# ADCMP.net
KiCad netlist of a schematic drawn in Altium Designer
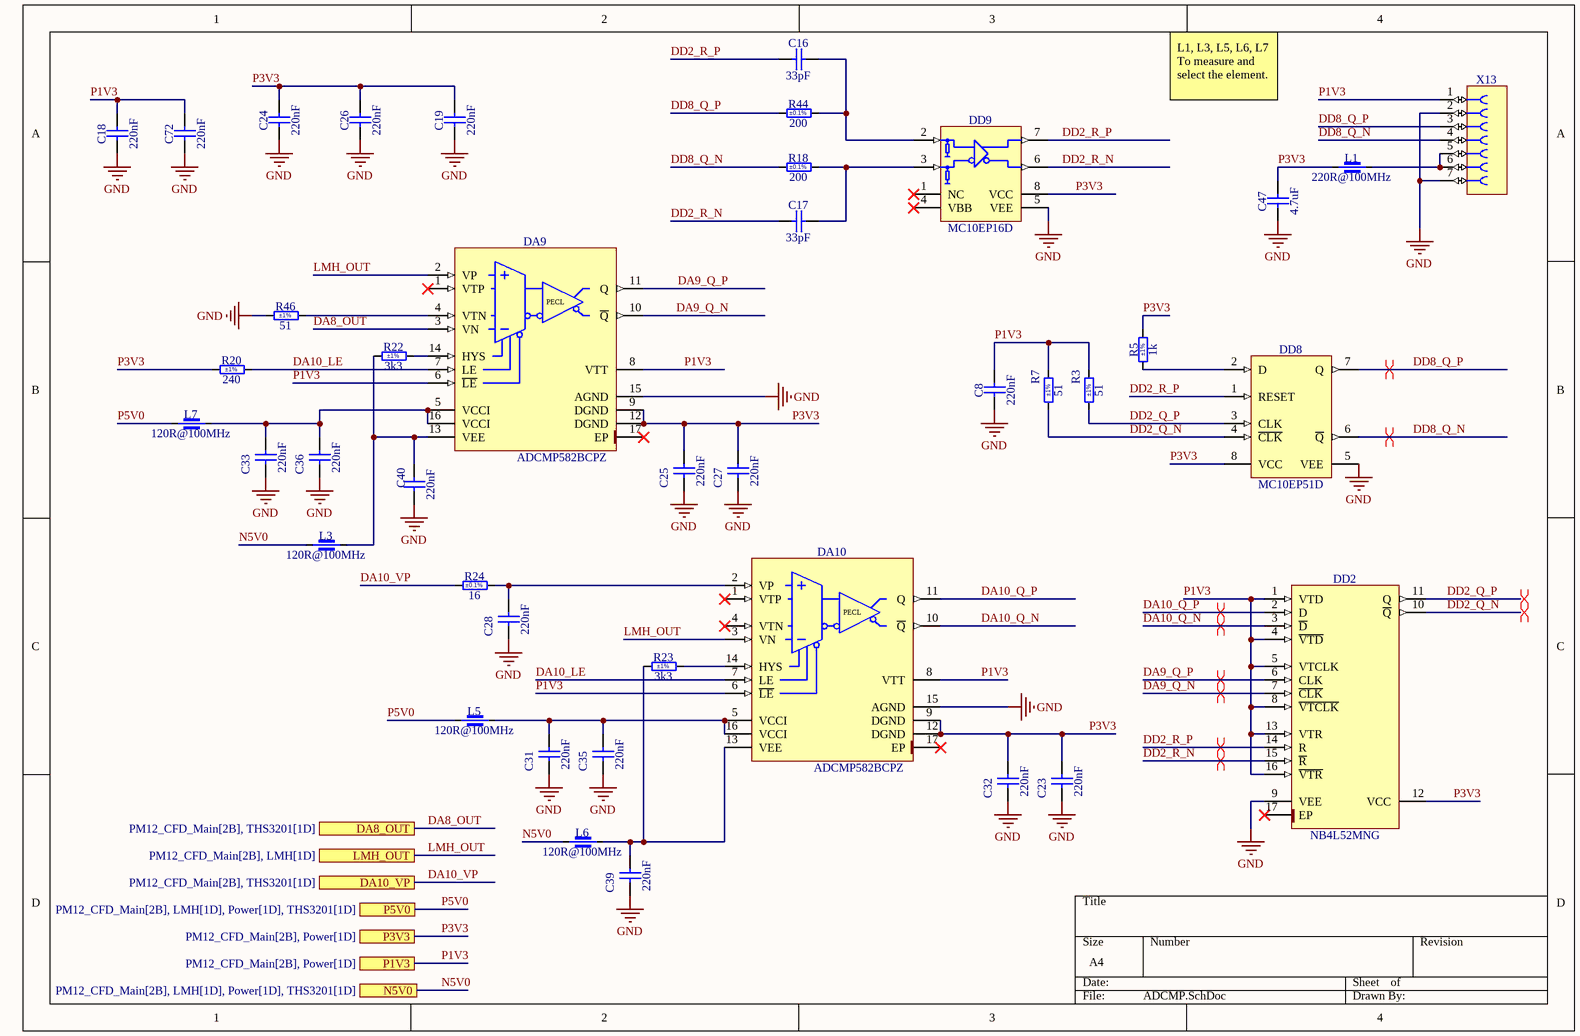
[diagram p0: ADCMP.SchDoc]

(export (version "E")
  (design (tool "Eeschema 10.0.6"))
  (components
    (comp (ref "C8")
      (value "220nF")
      (footprint "CAPC2012X135N")
      (description "Non-polarised capacitor")
      (fields
        (field (name "PART NUMBER") "CC0805_220NF_50V_10%_X7R")
        (field (name "VOLTAGE") "50V")
        (field (name "AUTHOR") "CERN DEM JLC")
      )
      (libsource (lib "Capacitors") (part "Capacitor - non polarized"))
    )
    (comp (ref "C16")
      (value "33pF")
      (footprint "CAPC2012X135N")
      (description "Non-polarised capacitor")
      (fields
        (field (name "PART NUMBER") "CC0805_33PF_50V_5%_NP0")
        (field (name "VOLTAGE") "50V")
        (field (name "AUTHOR") "CERN DEM JLC")
      )
      (libsource (lib "Capacitors") (part "Capacitor - non polarized"))
    )
    (comp (ref "C17")
      (value "33pF")
      (footprint "CAPC2012X135N")
      (description "Non-polarised capacitor")
      (fields
        (field (name "PART NUMBER") "CC0805_33PF_50V_5%_NP0")
        (field (name "VOLTAGE") "50V")
        (field (name "AUTHOR") "CERN DEM JLC")
      )
      (libsource (lib "Capacitors") (part "Capacitor - non polarized"))
    )
    (comp (ref "C18")
      (value "220nF")
      (footprint "CAPC1608X87N")
      (description "Non-polarised capacitor")
      (fields
        (field (name "PART NUMBER") "CC0603_220NF_25V_10%_X7R")
        (field (name "VOLTAGE") "25V")
        (field (name "AUTHOR") "CERN DEM JLC")
      )
      (libsource (lib "Capacitors") (part "Capacitor - non polarized"))
    )
    (comp (ref "C19")
      (value "220nF")
      (footprint "CAPC2012X135N")
      (description "Non-polarised capacitor")
      (fields
        (field (name "PART NUMBER") "CC0805_220NF_50V_10%_X7R")
        (field (name "VOLTAGE") "50V")
        (field (name "AUTHOR") "CERN DEM JLC")
      )
      (libsource (lib "Capacitors") (part "Capacitor - non polarized"))
    )
    (comp (ref "C23")
      (value "220nF")
      (footprint "CAPC1608X87N")
      (description "Non-polarised capacitor")
      (fields
        (field (name "PART NUMBER") "CC0603_220NF_25V_10%_X7R")
        (field (name "VOLTAGE") "25V")
        (field (name "AUTHOR") "CERN DEM JLC")
      )
      (libsource (lib "Capacitors") (part "Capacitor - non polarized"))
    )
    (comp (ref "C24")
      (value "220nF")
      (footprint "CAPC2012X135N")
      (description "Non-polarised capacitor")
      (fields
        (field (name "PART NUMBER") "CC0805_220NF_50V_10%_X7R")
        (field (name "VOLTAGE") "50V")
        (field (name "AUTHOR") "CERN DEM JLC")
      )
      (libsource (lib "Capacitors") (part "Capacitor - non polarized"))
    )
    (comp (ref "C25")
      (value "220nF")
      (footprint "CAPC1608X87N")
      (description "Non-polarised capacitor")
      (fields
        (field (name "PART NUMBER") "CC0603_220NF_25V_10%_X7R")
        (field (name "VOLTAGE") "25V")
        (field (name "AUTHOR") "CERN DEM JLC")
      )
      (libsource (lib "Capacitors") (part "Capacitor - non polarized"))
    )
    (comp (ref "C26")
      (value "220nF")
      (footprint "CAPC2012X135N")
      (description "Non-polarised capacitor")
      (fields
        (field (name "PART NUMBER") "CC0805_220NF_50V_10%_X7R")
        (field (name "VOLTAGE") "50V")
        (field (name "AUTHOR") "CERN DEM JLC")
      )
      (libsource (lib "Capacitors") (part "Capacitor - non polarized"))
    )
    (comp (ref "C27")
      (value "220nF")
      (footprint "CAPC1608X87N")
      (description "Non-polarised capacitor")
      (fields
        (field (name "PART NUMBER") "CC0603_220NF_25V_10%_X7R")
        (field (name "VOLTAGE") "25V")
        (field (name "AUTHOR") "CERN DEM JLC")
      )
      (libsource (lib "Capacitors") (part "Capacitor - non polarized"))
    )
    (comp (ref "C28")
      (value "220nF")
      (footprint "CAPC1608X87N")
      (description "Non-polarised capacitor")
      (fields
        (field (name "PART NUMBER") "CC0603_220NF_25V_10%_X7R")
        (field (name "VOLTAGE") "25V")
        (field (name "AUTHOR") "CERN DEM JLC")
      )
      (libsource (lib "Capacitors") (part "Capacitor - non polarized"))
    )
    (comp (ref "C31")
      (value "220nF")
      (footprint "CAPC1608X87N")
      (description "Non-polarised capacitor")
      (fields
        (field (name "PART NUMBER") "CC0603_220NF_25V_10%_X7R")
        (field (name "VOLTAGE") "25V")
        (field (name "AUTHOR") "CERN DEM JLC")
      )
      (libsource (lib "Capacitors") (part "Capacitor - non polarized"))
    )
    (comp (ref "C32")
      (value "220nF")
      (footprint "CAPC1608X87N")
      (description "Non-polarised capacitor")
      (fields
        (field (name "PART NUMBER") "CC0603_220NF_25V_10%_X7R")
        (field (name "VOLTAGE") "25V")
        (field (name "AUTHOR") "CERN DEM JLC")
      )
      (libsource (lib "Capacitors") (part "Capacitor - non polarized"))
    )
    (comp (ref "C33")
      (value "220nF")
      (footprint "CAPC1608X87N")
      (description "Non-polarised capacitor")
      (fields
        (field (name "PART NUMBER") "CC0603_220NF_25V_10%_X7R")
        (field (name "VOLTAGE") "25V")
        (field (name "AUTHOR") "CERN DEM JLC")
      )
      (libsource (lib "Capacitors") (part "Capacitor - non polarized"))
    )
    (comp (ref "C35")
      (value "220nF")
      (footprint "CAPC1608X87N")
      (description "Non-polarised capacitor")
      (fields
        (field (name "PART NUMBER") "CC0603_220NF_25V_10%_X7R")
        (field (name "VOLTAGE") "25V")
        (field (name "AUTHOR") "CERN DEM JLC")
      )
      (libsource (lib "Capacitors") (part "Capacitor - non polarized"))
    )
    (comp (ref "C36")
      (value "220nF")
      (footprint "CAPC1608X87N")
      (description "Non-polarised capacitor")
      (fields
        (field (name "PART NUMBER") "CC0603_220NF_25V_10%_X7R")
        (field (name "VOLTAGE") "25V")
        (field (name "AUTHOR") "CERN DEM JLC")
      )
      (libsource (lib "Capacitors") (part "Capacitor - non polarized"))
    )
    (comp (ref "C39")
      (value "220nF")
      (footprint "CAPC1608X87N")
      (description "Non-polarised capacitor")
      (fields
        (field (name "PART NUMBER") "CC0603_220NF_25V_10%_X7R")
        (field (name "VOLTAGE") "25V")
        (field (name "AUTHOR") "CERN DEM JLC")
      )
      (libsource (lib "Capacitors") (part "Capacitor - non polarized"))
    )
    (comp (ref "C40")
      (value "220nF")
      (footprint "CAPC1608X87N")
      (description "Non-polarised capacitor")
      (fields
        (field (name "PART NUMBER") "CC0603_220NF_25V_10%_X7R")
        (field (name "VOLTAGE") "25V")
        (field (name "AUTHOR") "CERN DEM JLC")
      )
      (libsource (lib "Capacitors") (part "Capacitor - non polarized"))
    )
    (comp (ref "C47")
      (value "4.7uF")
      (footprint "CAPC3216X180N")
      (description "Non-polarised capacitor")
      (fields
        (field (name "PART NUMBER") "CC1206_4.7UF_25V_10%_X7R")
        (field (name "VOLTAGE") "25V")
        (field (name "AUTHOR") "CERN DEM WB")
      )
      (libsource (lib "Capacitors") (part "Capacitor - non polarized"))
    )
    (comp (ref "C72")
      (value "220nF")
      (footprint "CAPC2012X135N")
      (description "Non-polarised capacitor")
      (fields
        (field (name "PART NUMBER") "CC0805_220NF_50V_10%_X7R")
        (field (name "VOLTAGE") "50V")
        (field (name "AUTHOR") "CERN DEM JLC")
      )
      (libsource (lib "Capacitors") (part "Capacitor - non polarized"))
    )
    (comp (ref "DA9")
      (value "ADCMP582BCPZ")
      (footprint "QFN50P300X300X80-17N-S145")
      (description "Ultrafast SiGe Voltage Comparator")
      (fields
        (field (name "MANUFACTURER") "ANALOG DEVICES")
        (field (name "MANUFACTURER PART NUMBER") "ADCMP582BCP")
        (field (name "AUTHOR") "CERN DEM MR")
      )
      (libsource (lib "ICs And Semiconductors") (part "ADCMP582BCPZ"))
    )
    (comp (ref "DA10")
      (value "ADCMP582BCPZ")
      (footprint "QFN50P300X300X80-17N-S145")
      (description "Ultrafast SiGe Voltage Comparator")
      (fields
        (field (name "MANUFACTURER") "ANALOG DEVICES")
        (field (name "MANUFACTURER PART NUMBER") "ADCMP582BCP")
        (field (name "AUTHOR") "CERN DEM MR")
      )
      (libsource (lib "ICs And Semiconductors") (part "ADCMP582BCPZ"))
    )
    (comp (ref "DD2")
      (value "NB4L52MNG")
      (footprint "QFN50P300X300X100-17N-S185")
      (description "2.5 V/3.3 V/5.0 V Differential Data/Clock D Flip-Flop with Reset")
      (fields
        (field (name "MANUFACTURER") "ON SEMICONDUCTOR")
        (field (name "MANUFACTURER PART NUMBER") "NB4L52MN")
        (field (name "AUTHOR") "CERN DEM MR")
      )
      (libsource (lib "ICs And Semiconductors") (part "NB4L52MN"))
    )
    (comp (ref "DD8")
      (value "MC10EP51D")
      (footprint "SOIC127P600X175-8N")
      (description "3.3V/5V ECL D Flip-Flop with Reset and Differential Clock")
      (fields (field (name "MANUFACTURER") "ON SEMICONDUCTOR") (field (name "AUTHOR") "CERN DEM HF"))
      (libsource (lib "ICs And Semiconductors") (part "10EP51"))
    )
    (comp (ref "DD9")
      (value "MC10EP16D")
      (footprint "SOIC127P600X175-8N")
      (description "3.3V / 5V ECL Differential Receiver/Driver")
      (fields (field (name "MANUFACTURER") "ON SEMICONDUCTOR") (field (name "AUTHOR") "CERN DEM HF"))
      (libsource (lib "ICs And Semiconductors") (part "10EP16"))
    )
    (comp (ref "L1")
      (value "220R@100MHz")
      (footprint "INDC2012X105N")
      (fields
        (field (name "PART NUMBER") "IND0805_TDK_MPZ2012S221A")
        (field (name "POWER") "3A")
        (field (name "TOLERANCE") "±25%")
        (field (name "AUTHOR") "CERN DEM HF")
      )
      (libsource (lib "Inductors & Transformers") (part "Ferrite Bead"))
    )
    (comp (ref "L3")
      (value "120R@100MHz")
      (footprint "INDC1608X95N")
      (fields
        (field (name "PART NUMBER") "IND0603_MURATA_BLM18PG121SN1D")
        (field (name "POWER") "2A")
        (field (name "MANUFACTURER") "MURATA")
        (field (name "AUTHOR") "CERN DEM BC")
      )
      (libsource (lib "Inductors & Transformers") (part "Ferrite Bead"))
    )
    (comp (ref "L5")
      (value "120R@100MHz")
      (footprint "INDC1608X95N")
      (fields
        (field (name "PART NUMBER") "IND0603_MURATA_BLM18PG121SN1D")
        (field (name "POWER") "2A")
        (field (name "MANUFACTURER") "MURATA")
        (field (name "AUTHOR") "CERN DEM BC")
      )
      (libsource (lib "Inductors & Transformers") (part "Ferrite Bead"))
    )
    (comp (ref "L6")
      (value "120R@100MHz")
      (footprint "INDC1608X95N")
      (fields
        (field (name "PART NUMBER") "IND0603_MURATA_BLM18PG121SN1D")
        (field (name "POWER") "2A")
        (field (name "MANUFACTURER") "MURATA")
        (field (name "AUTHOR") "CERN DEM BC")
      )
      (libsource (lib "Inductors & Transformers") (part "Ferrite Bead"))
    )
    (comp (ref "L7")
      (value "120R@100MHz")
      (footprint "INDC1608X95N")
      (fields
        (field (name "PART NUMBER") "IND0603_MURATA_BLM18PG121SN1D")
        (field (name "POWER") "2A")
        (field (name "MANUFACTURER") "MURATA")
        (field (name "AUTHOR") "CERN DEM BC")
      )
      (libsource (lib "Inductors & Transformers") (part "Ferrite Bead"))
    )
    (comp (ref "R3")
      (value "51")
      (footprint "RESC2012X60N")
      (description "Resistor - 1%")
      (fields
        (field (name "TOLERANCE") "±1%")
        (field (name "PART NUMBER") "R0805_51R_1%_0.125W_100PPM")
        (field (name "POWER") "0.125W")
        (field (name "AUTHOR") "CERN DEM JLC")
      )
      (libsource (lib "Resistors") (part "Resistor - 1%"))
    )
    (comp (ref "R5")
      (value "1k")
      (footprint "RESC2012X60N")
      (description "Resistor - 1%")
      (fields
        (field (name "TOLERANCE") "±1%")
        (field (name "PART NUMBER") "R0805_1K_1%_0.125W_100PPM")
        (field (name "POWER") "0.125W")
        (field (name "AUTHOR") "CERN DEM JLC")
      )
      (libsource (lib "Resistors") (part "Resistor - 1%"))
    )
    (comp (ref "R7")
      (value "51")
      (footprint "RESC2012X60N")
      (description "Resistor - 1%")
      (fields
        (field (name "TOLERANCE") "±1%")
        (field (name "PART NUMBER") "R0805_51R_1%_0.125W_100PPM")
        (field (name "POWER") "0.125W")
        (field (name "AUTHOR") "CERN DEM JLC")
      )
      (libsource (lib "Resistors") (part "Resistor - 1%"))
    )
    (comp (ref "R18")
      (value "200")
      (footprint "RESC2012X60N")
      (description "Resistor - 0.1%")
      (fields
        (field (name "TOLERANCE") "±0.1%")
        (field (name "PART NUMBER") "R0805_200R_0.1%_0.1W_10PPM")
        (field (name "POWER") "0.1W")
        (field (name "AUTHOR") "CERN DEM JLC")
      )
      (libsource (lib "Resistors") (part "Resistor - 0.1%"))
    )
    (comp (ref "R20")
      (value "240")
      (footprint "RESC1608X55N")
      (description "Resistor - 1%")
      (fields
        (field (name "TOLERANCE") "±1%")
        (field (name "PART NUMBER") "R0603_240R_1%_0.1W_100PPM")
        (field (name "POWER") "0.1W")
        (field (name "AUTHOR") "CERN DEM JLC")
      )
      (libsource (lib "Resistors") (part "Resistor - 1%"))
    )
    (comp (ref "R22")
      (value "3k3")
      (footprint "RESC1608X55N")
      (description "Resistor - 1%")
      (fields
        (field (name "TOLERANCE") "±1%")
        (field (name "PART NUMBER") "R0603_3K3_1%_0.1W_100PPM")
        (field (name "POWER") "0.1W")
        (field (name "AUTHOR") "CERN DEM JLC")
      )
      (libsource (lib "Resistors") (part "Resistor - 1%"))
    )
    (comp (ref "R23")
      (value "3k3")
      (footprint "RESC1608X55N")
      (description "Resistor - 1%")
      (fields
        (field (name "TOLERANCE") "±1%")
        (field (name "PART NUMBER") "R0603_3K3_1%_0.1W_100PPM")
        (field (name "POWER") "0.1W")
        (field (name "AUTHOR") "CERN DEM JLC")
      )
      (libsource (lib "Resistors") (part "Resistor - 1%"))
    )
    (comp (ref "R24")
      (value "16")
      (footprint "RESC1608X64N")
      (description "Resistor - 0.1%")
      (fields
        (field (name "TOLERANCE") "±0.1%")
        (field (name "PART NUMBER") "R0603_16R_0.1%_0.1W_10PPM")
        (field (name "POWER") "0.1W")
        (field (name "AUTHOR") "CERN DEM HF")
      )
      (libsource (lib "Resistors") (part "Resistor - 0.1%"))
    )
    (comp (ref "R44")
      (value "200")
      (footprint "RESC2012X60N")
      (description "Resistor - 0.1%")
      (fields
        (field (name "TOLERANCE") "±0.1%")
        (field (name "PART NUMBER") "R0805_200R_0.1%_0.1W_10PPM")
        (field (name "POWER") "0.1W")
        (field (name "AUTHOR") "CERN DEM JLC")
      )
      (libsource (lib "Resistors") (part "Resistor - 0.1%"))
    )
    (comp (ref "R46")
      (value "51")
      (footprint "RESC1608X55N")
      (description "Resistor - 1%")
      (fields
        (field (name "TOLERANCE") "±1%")
        (field (name "PART NUMBER") "R0603_51R_1%_0.1W_100PPM")
        (field (name "POWER") "0.1W")
        (field (name "AUTHOR") "CERN DEM JLC")
      )
      (libsource (lib "Resistors") (part "Resistor - 1%"))
    )
    (comp (ref "X13")
      (value "Socket 7")
      (footprint "SAMTEC_CES-107-01-T-S")
      (description "Connector 7 Female")
      (fields
        (field (name "PART NUMBER") "SAMTEC_CES-107-01-L-S")
        (field (name "MANUFACTURER") "SAMTEC")
        (field (name "AUTHOR") "CERN DEM HF")
      )
      (libsource (lib "Connectors") (part "Connector 7 Female"))
    )
  )
  (nets
    (net (code "1") (name "/DA8_OUT") (class "Default")
      (node (ref "DA9") (pin "3") (pinfunction "VN_3") (pintype "input"))
    )
    (net (code "2") (name "/DA9_Q_N") (class "Default")
      (node (ref "DA9") (pin "10") (pinfunction "~{Q}_10") (pintype "output"))
      (node (ref "DD2") (pin "7") (pinfunction "~{CLK}_7") (pintype "input"))
    )
    (net (code "3") (name "/DA9_Q_P") (class "Default")
      (node (ref "DA9") (pin "11") (pinfunction "Q_11") (pintype "output"))
      (node (ref "DD2") (pin "6") (pinfunction "CLK_6") (pintype "input"))
    )
    (net (code "4") (name "/DA10_LE") (class "Default")
      (node (ref "DA10") (pin "7") (pinfunction "LE_7") (pintype "input"))
      (node (ref "DA9") (pin "7") (pinfunction "LE_7") (pintype "input"))
      (node (ref "R20") (pin "2") (pinfunction "2_2") (pintype "passive"))
    )
    (net (code "5") (name "/DA10_Q_N") (class "Default")
      (node (ref "DA10") (pin "10") (pinfunction "~{Q}_10") (pintype "output"))
      (node (ref "DD2") (pin "3") (pinfunction "~{D}_3") (pintype "input"))
    )
    (net (code "6") (name "/DA10_Q_P") (class "Default")
      (node (ref "DA10") (pin "11") (pinfunction "Q_11") (pintype "output"))
      (node (ref "DD2") (pin "2") (pinfunction "D_2") (pintype "input"))
    )
    (net (code "7") (name "/DA10_VP") (class "Default")
      (node (ref "R24") (pin "1") (pinfunction "1_1") (pintype "passive"))
    )
    (net (code "8") (name "/DD2_Q_N") (class "Default")
      (node (ref "DD2") (pin "10") (pinfunction "~{Q}_10") (pintype "output"))
      (node (ref "DD8") (pin "4") (pinfunction "~{CLK}_4") (pintype "input"))
      (node (ref "R7") (pin "1") (pinfunction "1_1") (pintype "passive"))
    )
    (net (code "9") (name "/DD2_Q_P") (class "Default")
      (node (ref "DD2") (pin "11") (pinfunction "Q_11") (pintype "output"))
      (node (ref "DD8") (pin "3") (pinfunction "CLK_3") (pintype "input"))
      (node (ref "R3") (pin "1") (pinfunction "1_1") (pintype "passive"))
    )
    (net (code "10") (name "/DD2_R_N") (class "Default")
      (node (ref "C17") (pin "1") (pinfunction "1_1") (pintype "passive"))
      (node (ref "DD2") (pin "15") (pinfunction "~{R}_15") (pintype "input"))
      (node (ref "DD9") (pin "6") (pinfunction "~{Q}_6") (pintype "output"))
    )
    (net (code "11") (name "/DD2_R_P") (class "Default")
      (node (ref "C16") (pin "1") (pinfunction "1_1") (pintype "passive"))
      (node (ref "DD2") (pin "14") (pinfunction "R_14") (pintype "input"))
      (node (ref "DD8") (pin "1") (pinfunction "RESET_1") (pintype "input"))
      (node (ref "DD9") (pin "7") (pinfunction "Q_7") (pintype "output"))
    )
    (net (code "12") (name "/DD8_Q_N") (class "Default")
      (node (ref "DD8") (pin "6") (pinfunction "~{Q}_6") (pintype "output"))
      (node (ref "R18") (pin "1") (pinfunction "1_1") (pintype "passive"))
      (node (ref "X13") (pin "4") (pinfunction "4_4") (pintype "bidirectional"))
    )
    (net (code "13") (name "/DD8_Q_P") (class "Default")
      (node (ref "DD8") (pin "7") (pinfunction "Q_7") (pintype "output"))
      (node (ref "R44") (pin "1") (pinfunction "1_1") (pintype "passive"))
      (node (ref "X13") (pin "3") (pinfunction "3_3") (pintype "bidirectional"))
    )
    (net (code "14") (name "/LMH_OUT") (class "Default")
      (node (ref "DA10") (pin "3") (pinfunction "VN_3") (pintype "input"))
      (node (ref "DA9") (pin "2") (pinfunction "VP_2") (pintype "input"))
    )
    (net (code "15") (name "/N5V0") (class "Default")
      (node (ref "L3") (pin "1") (pinfunction "1_1") (pintype "passive"))
      (node (ref "L6") (pin "1") (pinfunction "1_1") (pintype "passive"))
    )
    (net (code "16") (name "/P1V3") (class "Default")
      (node (ref "C18") (pin "2") (pinfunction "2_2") (pintype "passive"))
      (node (ref "C72") (pin "2") (pinfunction "2_2") (pintype "passive"))
      (node (ref "C8") (pin "2") (pinfunction "2_2") (pintype "passive"))
      (node (ref "DA10") (pin "6") (pinfunction "~{LE}_6") (pintype "input"))
      (node (ref "DA10") (pin "8") (pinfunction "VTT_8") (pintype "power_in"))
      (node (ref "DA9") (pin "6") (pinfunction "~{LE}_6") (pintype "input"))
      (node (ref "DA9") (pin "8") (pinfunction "VTT_8") (pintype "power_in"))
      (node (ref "DD2") (pin "1") (pinfunction "VTD_1") (pintype "input"))
      (node (ref "DD2") (pin "13") (pinfunction "VTR_13") (pintype "input"))
      (node (ref "DD2") (pin "16") (pinfunction "~{VTR}_16") (pintype "input"))
      (node (ref "DD2") (pin "4") (pinfunction "~{VTD}_4") (pintype "input"))
      (node (ref "DD2") (pin "5") (pinfunction "VTCLK_5") (pintype "input"))
      (node (ref "DD2") (pin "8") (pinfunction "~{VTCLK}_8") (pintype "input"))
      (node (ref "R3") (pin "2") (pinfunction "2_2") (pintype "passive"))
      (node (ref "R7") (pin "2") (pinfunction "2_2") (pintype "passive"))
      (node (ref "X13") (pin "1") (pinfunction "1_1") (pintype "bidirectional"))
    )
    (net (code "17") (name "/P3V3") (class "Default")
      (node (ref "C19") (pin "2") (pinfunction "2_2") (pintype "passive"))
      (node (ref "C23") (pin "2") (pinfunction "2_2") (pintype "passive"))
      (node (ref "C24") (pin "2") (pinfunction "2_2") (pintype "passive"))
      (node (ref "C25") (pin "2") (pinfunction "2_2") (pintype "passive"))
      (node (ref "C26") (pin "2") (pinfunction "2_2") (pintype "passive"))
      (node (ref "C27") (pin "2") (pinfunction "2_2") (pintype "passive"))
      (node (ref "C32") (pin "2") (pinfunction "2_2") (pintype "passive"))
      (node (ref "C47") (pin "2") (pinfunction "2_2") (pintype "passive"))
      (node (ref "DA10") (pin "12") (pinfunction "DGND_12") (pintype "power_in"))
      (node (ref "DA10") (pin "9") (pinfunction "DGND_9") (pintype "power_in"))
      (node (ref "DA9") (pin "12") (pinfunction "DGND_12") (pintype "power_in"))
      (node (ref "DA9") (pin "9") (pinfunction "DGND_9") (pintype "power_in"))
      (node (ref "DD2") (pin "12") (pinfunction "VCC_12") (pintype "power_in"))
      (node (ref "DD8") (pin "8") (pinfunction "VCC_8") (pintype "power_in"))
      (node (ref "DD9") (pin "8") (pinfunction "VCC_8") (pintype "power_in"))
      (node (ref "L1") (pin "1") (pinfunction "1_1") (pintype "passive"))
      (node (ref "R20") (pin "1") (pinfunction "1_1") (pintype "passive"))
      (node (ref "R5") (pin "2") (pinfunction "2_2") (pintype "passive"))
    )
    (net (code "18") (name "/P5V0") (class "Default")
      (node (ref "L5") (pin "1") (pinfunction "1_1") (pintype "passive"))
      (node (ref "L7") (pin "1") (pinfunction "1_1") (pintype "passive"))
    )
    (net (code "19") (name "GND") (class "Default")
      (node (ref "C18") (pin "1") (pinfunction "1_1") (pintype "passive"))
      (node (ref "C19") (pin "1") (pinfunction "1_1") (pintype "passive"))
      (node (ref "C23") (pin "1") (pinfunction "1_1") (pintype "passive"))
      (node (ref "C24") (pin "1") (pinfunction "1_1") (pintype "passive"))
      (node (ref "C25") (pin "1") (pinfunction "1_1") (pintype "passive"))
      (node (ref "C26") (pin "1") (pinfunction "1_1") (pintype "passive"))
      (node (ref "C27") (pin "1") (pinfunction "1_1") (pintype "passive"))
      (node (ref "C28") (pin "1") (pinfunction "1_1") (pintype "passive"))
      (node (ref "C31") (pin "1") (pinfunction "1_1") (pintype "passive"))
      (node (ref "C32") (pin "1") (pinfunction "1_1") (pintype "passive"))
      (node (ref "C33") (pin "1") (pinfunction "1_1") (pintype "passive"))
      (node (ref "C35") (pin "1") (pinfunction "1_1") (pintype "passive"))
      (node (ref "C36") (pin "1") (pinfunction "1_1") (pintype "passive"))
      (node (ref "C39") (pin "1") (pinfunction "1_1") (pintype "passive"))
      (node (ref "C40") (pin "1") (pinfunction "1_1") (pintype "passive"))
      (node (ref "C47") (pin "1") (pinfunction "1_1") (pintype "passive"))
      (node (ref "C72") (pin "1") (pinfunction "1_1") (pintype "passive"))
      (node (ref "C8") (pin "1") (pinfunction "1_1") (pintype "passive"))
      (node (ref "DA10") (pin "15") (pinfunction "AGND_15") (pintype "power_in"))
      (node (ref "DA9") (pin "15") (pinfunction "AGND_15") (pintype "power_in"))
      (node (ref "DD2") (pin "9") (pinfunction "VEE_9") (pintype "power_in"))
      (node (ref "DD8") (pin "5") (pinfunction "VEE_5") (pintype "power_in"))
      (node (ref "DD9") (pin "5") (pinfunction "VEE_5") (pintype "power_in"))
      (node (ref "R46") (pin "1") (pinfunction "1_1") (pintype "passive"))
      (node (ref "X13") (pin "2") (pinfunction "2_2") (pintype "bidirectional"))
      (node (ref "X13") (pin "7") (pinfunction "7_7") (pintype "bidirectional"))
    )
    (net (code "20") (name "Net-(C31-Pad2)") (class "Default")
      (node (ref "C31") (pin "2") (pinfunction "2_2") (pintype "passive"))
      (node (ref "C35") (pin "2") (pinfunction "2_2") (pintype "passive"))
      (node (ref "DA10") (pin "16") (pinfunction "VCCI_16") (pintype "power_in"))
      (node (ref "DA10") (pin "5") (pinfunction "VCCI_5") (pintype "power_in"))
      (node (ref "L5") (pin "2") (pinfunction "2_2") (pintype "passive"))
    )
    (net (code "21") (name "Net-(C33-Pad2)") (class "Default")
      (node (ref "C33") (pin "2") (pinfunction "2_2") (pintype "passive"))
      (node (ref "C36") (pin "2") (pinfunction "2_2") (pintype "passive"))
      (node (ref "DA9") (pin "16") (pinfunction "VCCI_16") (pintype "power_in"))
      (node (ref "DA9") (pin "5") (pinfunction "VCCI_5") (pintype "power_in"))
      (node (ref "L7") (pin "2") (pinfunction "2_2") (pintype "passive"))
    )
    (net (code "22") (name "Net-(DA9-HYS)") (class "Default")
      (node (ref "DA9") (pin "14") (pinfunction "HYS_14") (pintype "input"))
      (node (ref "R22") (pin "2") (pinfunction "2_2") (pintype "passive"))
    )
    (net (code "23") (name "Net-(DA9-VEE)") (class "Default")
      (node (ref "C40") (pin "2") (pinfunction "2_2") (pintype "passive"))
      (node (ref "DA9") (pin "13") (pinfunction "VEE_13") (pintype "power_in"))
      (node (ref "L3") (pin "2") (pinfunction "2_2") (pintype "passive"))
      (node (ref "R22") (pin "1") (pinfunction "1_1") (pintype "passive"))
    )
    (net (code "24") (name "Net-(DA9-VTN)") (class "Default")
      (node (ref "DA9") (pin "4") (pinfunction "VTN_4") (pintype "input"))
      (node (ref "R46") (pin "2") (pinfunction "2_2") (pintype "passive"))
    )
    (net (code "25") (name "Net-(DA10-HYS)") (class "Default")
      (node (ref "DA10") (pin "14") (pinfunction "HYS_14") (pintype "input"))
      (node (ref "R23") (pin "2") (pinfunction "2_2") (pintype "passive"))
    )
    (net (code "26") (name "Net-(DA10-VEE)") (class "Default")
      (node (ref "C39") (pin "2") (pinfunction "2_2") (pintype "passive"))
      (node (ref "DA10") (pin "13") (pinfunction "VEE_13") (pintype "power_in"))
      (node (ref "L6") (pin "2") (pinfunction "2_2") (pintype "passive"))
      (node (ref "R23") (pin "1") (pinfunction "1_1") (pintype "passive"))
    )
    (net (code "27") (name "Net-(DA10-VP)") (class "Default")
      (node (ref "C28") (pin "2") (pinfunction "2_2") (pintype "passive"))
      (node (ref "DA10") (pin "2") (pinfunction "VP_2") (pintype "input"))
      (node (ref "R24") (pin "2") (pinfunction "2_2") (pintype "passive"))
    )
    (net (code "28") (name "Net-(DD8-D)") (class "Default")
      (node (ref "DD8") (pin "2") (pinfunction "D_2") (pintype "input"))
      (node (ref "R5") (pin "1") (pinfunction "1_1") (pintype "passive"))
    )
    (net (code "29") (name "Net-(DD9-D0)") (class "Default")
      (node (ref "C16") (pin "2") (pinfunction "2_2") (pintype "passive"))
      (node (ref "DD9") (pin "2") (pinfunction "D0_2") (pintype "input"))
      (node (ref "R44") (pin "2") (pinfunction "2_2") (pintype "passive"))
    )
    (net (code "30") (name "Net-(DD9-~{D0})") (class "Default")
      (node (ref "C17") (pin "2") (pinfunction "2_2") (pintype "passive"))
      (node (ref "DD9") (pin "3") (pinfunction "~{D0}_3") (pintype "input"))
      (node (ref "R18") (pin "2") (pinfunction "2_2") (pintype "passive"))
    )
    (net (code "31") (name "Net-(L1-Pad2)") (class "Default")
      (node (ref "L1") (pin "2") (pinfunction "2_2") (pintype "passive"))
      (node (ref "X13") (pin "5") (pinfunction "5_5") (pintype "bidirectional"))
      (node (ref "X13") (pin "6") (pinfunction "6_6") (pintype "bidirectional"))
    )
    (net (code "32") (name "unconnected-(DA9-EP-Pad17)") (class "Default")
      (node (ref "DA9") (pin "17") (pinfunction "EP_17") (pintype "power_in+no_connect"))
    )
    (net (code "33") (name "unconnected-(DA9-VTP-Pad1)") (class "Default")
      (node (ref "DA9") (pin "1") (pinfunction "VTP_1") (pintype "input+no_connect"))
    )
    (net (code "34") (name "unconnected-(DA10-EP-Pad17)") (class "Default")
      (node (ref "DA10") (pin "17") (pinfunction "EP_17") (pintype "power_in+no_connect"))
    )
    (net (code "35") (name "unconnected-(DA10-VTN-Pad4)") (class "Default")
      (node (ref "DA10") (pin "4") (pinfunction "VTN_4") (pintype "input+no_connect"))
    )
    (net (code "36") (name "unconnected-(DA10-VTP-Pad1)") (class "Default")
      (node (ref "DA10") (pin "1") (pinfunction "VTP_1") (pintype "input+no_connect"))
    )
    (net (code "37") (name "unconnected-(DD2-EP-Pad17)") (class "Default")
      (node (ref "DD2") (pin "17") (pinfunction "EP_17") (pintype "power_in+no_connect"))
    )
    (net (code "38") (name "unconnected-(DD9-NC-Pad1)") (class "Default")
      (node (ref "DD9") (pin "1") (pinfunction "NC_1") (pintype "passive+no_connect"))
    )
    (net (code "39") (name "unconnected-(DD9-VBB-Pad4)") (class "Default")
      (node (ref "DD9") (pin "4") (pinfunction "VBB_4") (pintype "power_in+no_connect"))
    )
  )
)
